# PGTN034_quantizer_mki_controls.net
KiCad netlist of a schematic drawn in EAGLE
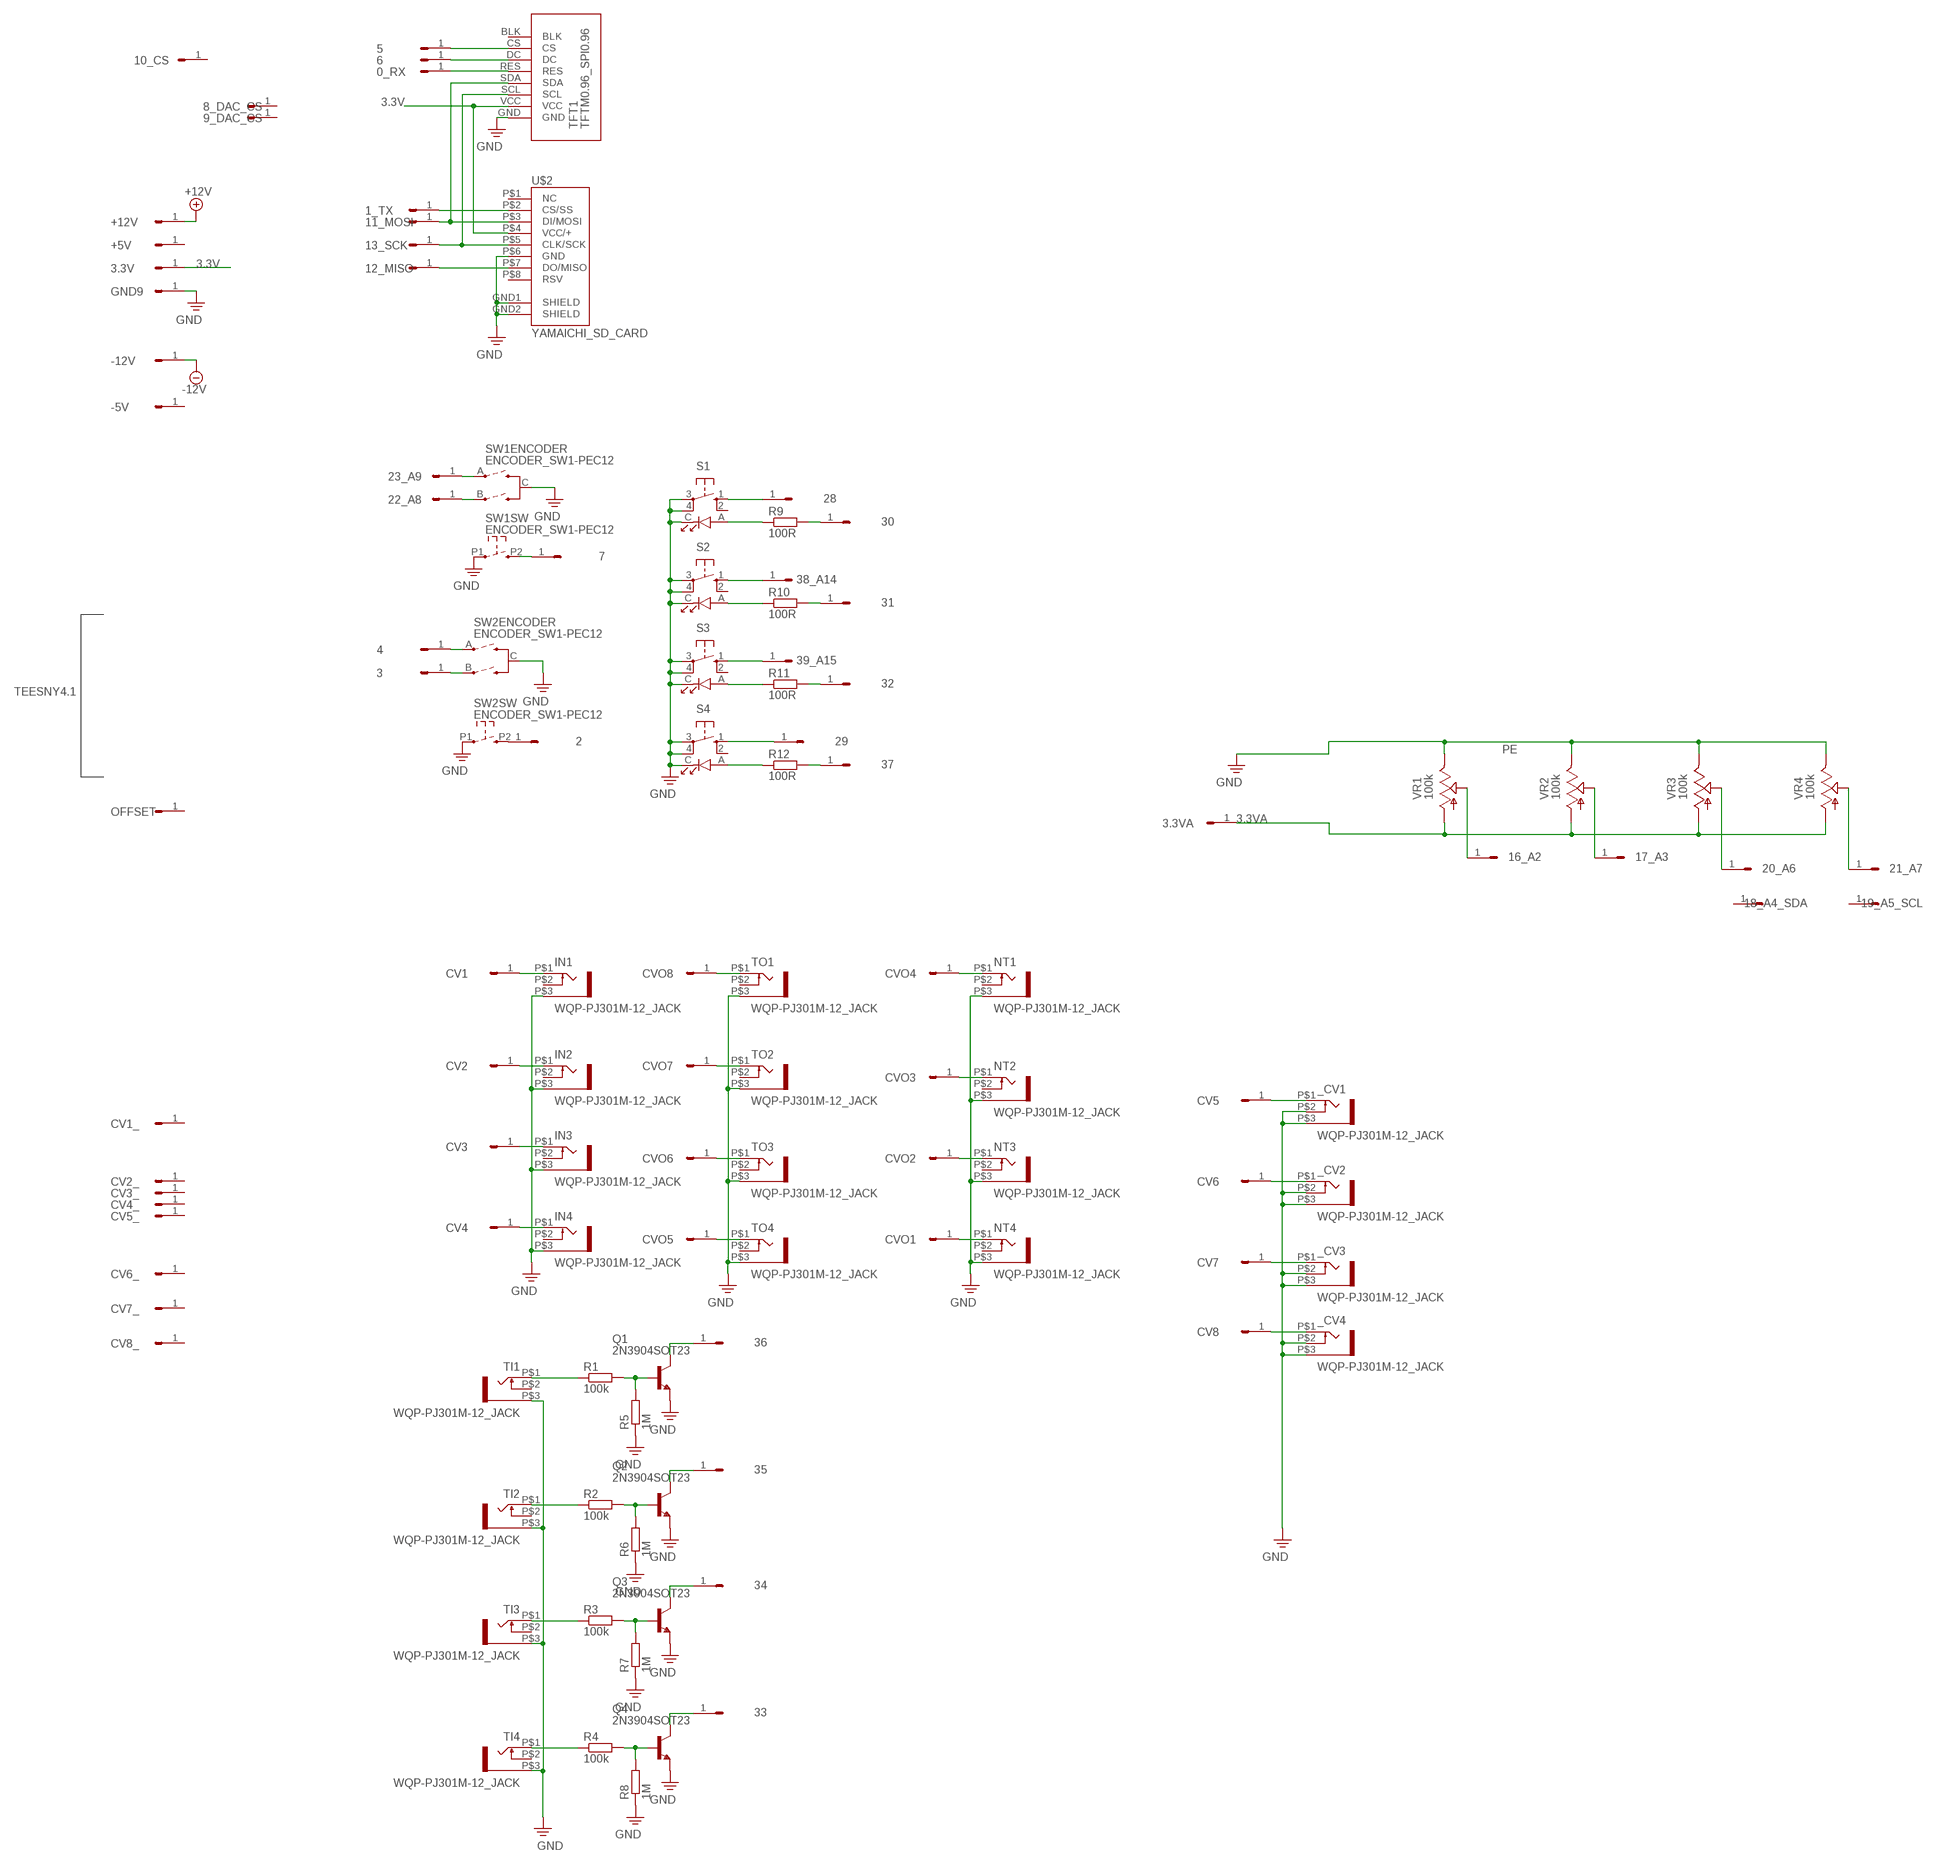
[diagram p0: schematic, sheet 1]

(export (version "E")
  (design (tool "Eeschema 10.0.6"))
  (components
    (comp (ref "+5V")
      (value "HEADER/MALE/01")
      (footprint "eagle-import:HEADER_MALE_01")
      (fields (field (name "SPICEPREFIX") "X"))
      (libsource (lib "eagle-import") (part "HEADER/MALE/01"))
    )
    (comp (ref "+12V")
      (value "HEADER/MALE/01")
      (footprint "eagle-import:HEADER_MALE_01")
      (fields (field (name "SPICEPREFIX") "X"))
      (libsource (lib "eagle-import") (part "HEADER/MALE/01"))
    )
    (comp (ref "-5V")
      (value "HEADER/MALE/01")
      (footprint "eagle-import:HEADER_MALE_01")
      (fields (field (name "SPICEPREFIX") "X"))
      (libsource (lib "eagle-import") (part "HEADER/MALE/01"))
    )
    (comp (ref "-12V")
      (value "HEADER/MALE/01")
      (footprint "eagle-import:HEADER_MALE_01")
      (fields (field (name "SPICEPREFIX") "X"))
      (libsource (lib "eagle-import") (part "HEADER/MALE/01"))
    )
    (comp (ref "0_RX")
      (value "HEADER/MALE/01")
      (footprint "eagle-import:HEADER_MALE_01")
      (fields (field (name "SPICEPREFIX") "X"))
      (libsource (lib "eagle-import") (part "HEADER/MALE/01"))
    )
    (comp (ref "1_TX")
      (value "HEADER/MALE/01")
      (footprint "eagle-import:HEADER_MALE_01")
      (fields (field (name "SPICEPREFIX") "X"))
      (libsource (lib "eagle-import") (part "HEADER/MALE/01"))
    )
    (comp (ref "2")
      (value "HEADER/MALE/01")
      (footprint "eagle-import:HEADER_MALE_01")
      (fields (field (name "SPICEPREFIX") "X"))
      (libsource (lib "eagle-import") (part "HEADER/MALE/01"))
    )
    (comp (ref "3")
      (value "HEADER/MALE/01")
      (footprint "eagle-import:HEADER_MALE_01")
      (fields (field (name "SPICEPREFIX") "X"))
      (libsource (lib "eagle-import") (part "HEADER/MALE/01"))
    )
    (comp (ref "3.3V")
      (value "HEADER/MALE/01")
      (footprint "eagle-import:HEADER_MALE_01")
      (fields (field (name "SPICEPREFIX") "X"))
      (libsource (lib "eagle-import") (part "HEADER/MALE/01"))
    )
    (comp (ref "3.3VA")
      (value "HEADER/MALE/01")
      (footprint "eagle-import:HEADER_MALE_01")
      (fields (field (name "SPICEPREFIX") "X"))
      (libsource (lib "eagle-import") (part "HEADER/MALE/01"))
    )
    (comp (ref "4")
      (value "HEADER/MALE/01")
      (footprint "eagle-import:HEADER_MALE_01")
      (fields (field (name "SPICEPREFIX") "X"))
      (libsource (lib "eagle-import") (part "HEADER/MALE/01"))
    )
    (comp (ref "5")
      (value "HEADER/MALE/01")
      (footprint "eagle-import:HEADER_MALE_01")
      (fields (field (name "SPICEPREFIX") "X"))
      (libsource (lib "eagle-import") (part "HEADER/MALE/01"))
    )
    (comp (ref "6")
      (value "HEADER/MALE/01")
      (footprint "eagle-import:HEADER_MALE_01")
      (fields (field (name "SPICEPREFIX") "X"))
      (libsource (lib "eagle-import") (part "HEADER/MALE/01"))
    )
    (comp (ref "7")
      (value "HEADER/MALE/01")
      (footprint "eagle-import:HEADER_MALE_01")
      (fields (field (name "SPICEPREFIX") "X"))
      (libsource (lib "eagle-import") (part "HEADER/MALE/01"))
    )
    (comp (ref "8_DAC_CS")
      (value "HEADER/MALE/01")
      (footprint "eagle-import:HEADER_MALE_01")
      (fields (field (name "SPICEPREFIX") "X"))
      (libsource (lib "eagle-import") (part "HEADER/MALE/01"))
    )
    (comp (ref "9_DAC_CS")
      (value "HEADER/MALE/01")
      (footprint "eagle-import:HEADER_MALE_01")
      (fields (field (name "SPICEPREFIX") "X"))
      (libsource (lib "eagle-import") (part "HEADER/MALE/01"))
    )
    (comp (ref "10_CS")
      (value "HEADER/MALE/01")
      (footprint "eagle-import:HEADER_MALE_01")
      (fields (field (name "SPICEPREFIX") "X"))
      (libsource (lib "eagle-import") (part "HEADER/MALE/01"))
    )
    (comp (ref "11_MOSI")
      (value "HEADER/MALE/01")
      (footprint "eagle-import:HEADER_MALE_01")
      (fields (field (name "SPICEPREFIX") "X"))
      (libsource (lib "eagle-import") (part "HEADER/MALE/01"))
    )
    (comp (ref "12_MISO")
      (value "HEADER/MALE/01")
      (footprint "eagle-import:HEADER_MALE_01")
      (fields (field (name "SPICEPREFIX") "X"))
      (libsource (lib "eagle-import") (part "HEADER/MALE/01"))
    )
    (comp (ref "13_SCK")
      (value "HEADER/MALE/01")
      (footprint "eagle-import:HEADER_MALE_01")
      (fields (field (name "SPICEPREFIX") "X"))
      (libsource (lib "eagle-import") (part "HEADER/MALE/01"))
    )
    (comp (ref "16_A2")
      (value "HEADER/MALE/01")
      (footprint "eagle-import:HEADER_MALE_01")
      (fields (field (name "SPICEPREFIX") "X"))
      (libsource (lib "eagle-import") (part "HEADER/MALE/01"))
    )
    (comp (ref "17_A3")
      (value "HEADER/MALE/01")
      (footprint "eagle-import:HEADER_MALE_01")
      (fields (field (name "SPICEPREFIX") "X"))
      (libsource (lib "eagle-import") (part "HEADER/MALE/01"))
    )
    (comp (ref "18_A4_SDA")
      (value "HEADER/MALE/01")
      (footprint "eagle-import:HEADER_MALE_01")
      (fields (field (name "SPICEPREFIX") "X"))
      (libsource (lib "eagle-import") (part "HEADER/MALE/01"))
    )
    (comp (ref "19_A5_SCL")
      (value "HEADER/MALE/01")
      (footprint "eagle-import:HEADER_MALE_01")
      (fields (field (name "SPICEPREFIX") "X"))
      (libsource (lib "eagle-import") (part "HEADER/MALE/01"))
    )
    (comp (ref "20_A6")
      (value "HEADER/MALE/01")
      (footprint "eagle-import:HEADER_MALE_01")
      (fields (field (name "SPICEPREFIX") "X"))
      (libsource (lib "eagle-import") (part "HEADER/MALE/01"))
    )
    (comp (ref "21_A7")
      (value "HEADER/MALE/01")
      (footprint "eagle-import:HEADER_MALE_01")
      (fields (field (name "SPICEPREFIX") "X"))
      (libsource (lib "eagle-import") (part "HEADER/MALE/01"))
    )
    (comp (ref "22_A8")
      (value "HEADER/MALE/01")
      (footprint "eagle-import:HEADER_MALE_01")
      (fields (field (name "SPICEPREFIX") "X"))
      (libsource (lib "eagle-import") (part "HEADER/MALE/01"))
    )
    (comp (ref "23_A9")
      (value "HEADER/MALE/01")
      (footprint "eagle-import:HEADER_MALE_01")
      (fields (field (name "SPICEPREFIX") "X"))
      (libsource (lib "eagle-import") (part "HEADER/MALE/01"))
    )
    (comp (ref "28")
      (value "HEADER/MALE/01")
      (footprint "eagle-import:HEADER_MALE_01")
      (fields (field (name "SPICEPREFIX") "X"))
      (libsource (lib "eagle-import") (part "HEADER/MALE/01"))
    )
    (comp (ref "29")
      (value "HEADER/MALE/01")
      (footprint "eagle-import:HEADER_MALE_01")
      (fields (field (name "SPICEPREFIX") "X"))
      (libsource (lib "eagle-import") (part "HEADER/MALE/01"))
    )
    (comp (ref "30")
      (value "HEADER/MALE/01")
      (footprint "eagle-import:HEADER_MALE_01")
      (fields (field (name "SPICEPREFIX") "X"))
      (libsource (lib "eagle-import") (part "HEADER/MALE/01"))
    )
    (comp (ref "31")
      (value "HEADER/MALE/01")
      (footprint "eagle-import:HEADER_MALE_01")
      (fields (field (name "SPICEPREFIX") "X"))
      (libsource (lib "eagle-import") (part "HEADER/MALE/01"))
    )
    (comp (ref "32")
      (value "HEADER/MALE/01")
      (footprint "eagle-import:HEADER_MALE_01")
      (fields (field (name "SPICEPREFIX") "X"))
      (libsource (lib "eagle-import") (part "HEADER/MALE/01"))
    )
    (comp (ref "33")
      (value "HEADER/MALE/01")
      (footprint "eagle-import:HEADER_MALE_01")
      (fields (field (name "SPICEPREFIX") "X"))
      (libsource (lib "eagle-import") (part "HEADER/MALE/01"))
    )
    (comp (ref "34")
      (value "HEADER/MALE/01")
      (footprint "eagle-import:HEADER_MALE_01")
      (fields (field (name "SPICEPREFIX") "X"))
      (libsource (lib "eagle-import") (part "HEADER/MALE/01"))
    )
    (comp (ref "35")
      (value "HEADER/MALE/01")
      (footprint "eagle-import:HEADER_MALE_01")
      (fields (field (name "SPICEPREFIX") "X"))
      (libsource (lib "eagle-import") (part "HEADER/MALE/01"))
    )
    (comp (ref "36")
      (value "HEADER/MALE/01")
      (footprint "eagle-import:HEADER_MALE_01")
      (fields (field (name "SPICEPREFIX") "X"))
      (libsource (lib "eagle-import") (part "HEADER/MALE/01"))
    )
    (comp (ref "37")
      (value "HEADER/MALE/01")
      (footprint "eagle-import:HEADER_MALE_01")
      (fields (field (name "SPICEPREFIX") "X"))
      (libsource (lib "eagle-import") (part "HEADER/MALE/01"))
    )
    (comp (ref "38_A14")
      (value "HEADER/MALE/01")
      (footprint "eagle-import:HEADER_MALE_01")
      (fields (field (name "SPICEPREFIX") "X"))
      (libsource (lib "eagle-import") (part "HEADER/MALE/01"))
    )
    (comp (ref "39_A15")
      (value "HEADER/MALE/01")
      (footprint "eagle-import:HEADER_MALE_01")
      (fields (field (name "SPICEPREFIX") "X"))
      (libsource (lib "eagle-import") (part "HEADER/MALE/01"))
    )
    (comp (ref "CV1")
      (value "HEADER/MALE/01")
      (footprint "eagle-import:HEADER_MALE_01")
      (fields (field (name "SPICEPREFIX") "X"))
      (libsource (lib "eagle-import") (part "HEADER/MALE/01"))
    )
    (comp (ref "CV1_")
      (value "HEADER/MALE/01")
      (footprint "eagle-import:HEADER_MALE_01")
      (fields (field (name "SPICEPREFIX") "X"))
      (libsource (lib "eagle-import") (part "HEADER/MALE/01"))
    )
    (comp (ref "CV2")
      (value "HEADER/MALE/01")
      (footprint "eagle-import:HEADER_MALE_01")
      (fields (field (name "SPICEPREFIX") "X"))
      (libsource (lib "eagle-import") (part "HEADER/MALE/01"))
    )
    (comp (ref "CV2_")
      (value "HEADER/MALE/01")
      (footprint "eagle-import:HEADER_MALE_01")
      (fields (field (name "SPICEPREFIX") "X"))
      (libsource (lib "eagle-import") (part "HEADER/MALE/01"))
    )
    (comp (ref "CV3")
      (value "HEADER/MALE/01")
      (footprint "eagle-import:HEADER_MALE_01")
      (fields (field (name "SPICEPREFIX") "X"))
      (libsource (lib "eagle-import") (part "HEADER/MALE/01"))
    )
    (comp (ref "CV3_")
      (value "HEADER/MALE/01")
      (footprint "eagle-import:HEADER_MALE_01")
      (fields (field (name "SPICEPREFIX") "X"))
      (libsource (lib "eagle-import") (part "HEADER/MALE/01"))
    )
    (comp (ref "CV4")
      (value "HEADER/MALE/01")
      (footprint "eagle-import:HEADER_MALE_01")
      (fields (field (name "SPICEPREFIX") "X"))
      (libsource (lib "eagle-import") (part "HEADER/MALE/01"))
    )
    (comp (ref "CV4_")
      (value "HEADER/MALE/01")
      (footprint "eagle-import:HEADER_MALE_01")
      (fields (field (name "SPICEPREFIX") "X"))
      (libsource (lib "eagle-import") (part "HEADER/MALE/01"))
    )
    (comp (ref "CV5")
      (value "HEADER/MALE/01")
      (footprint "eagle-import:HEADER_MALE_01")
      (fields (field (name "SPICEPREFIX") "X"))
      (libsource (lib "eagle-import") (part "HEADER/MALE/01"))
    )
    (comp (ref "CV5_")
      (value "HEADER/MALE/01")
      (footprint "eagle-import:HEADER_MALE_01")
      (fields (field (name "SPICEPREFIX") "X"))
      (libsource (lib "eagle-import") (part "HEADER/MALE/01"))
    )
    (comp (ref "CV6")
      (value "HEADER/MALE/01")
      (footprint "eagle-import:HEADER_MALE_01")
      (fields (field (name "SPICEPREFIX") "X"))
      (libsource (lib "eagle-import") (part "HEADER/MALE/01"))
    )
    (comp (ref "CV6_")
      (value "HEADER/MALE/01")
      (footprint "eagle-import:HEADER_MALE_01")
      (fields (field (name "SPICEPREFIX") "X"))
      (libsource (lib "eagle-import") (part "HEADER/MALE/01"))
    )
    (comp (ref "CV7")
      (value "HEADER/MALE/01")
      (footprint "eagle-import:HEADER_MALE_01")
      (fields (field (name "SPICEPREFIX") "X"))
      (libsource (lib "eagle-import") (part "HEADER/MALE/01"))
    )
    (comp (ref "CV7_")
      (value "HEADER/MALE/01")
      (footprint "eagle-import:HEADER_MALE_01")
      (fields (field (name "SPICEPREFIX") "X"))
      (libsource (lib "eagle-import") (part "HEADER/MALE/01"))
    )
    (comp (ref "CV8")
      (value "HEADER/MALE/01")
      (footprint "eagle-import:HEADER_MALE_01")
      (fields (field (name "SPICEPREFIX") "X"))
      (libsource (lib "eagle-import") (part "HEADER/MALE/01"))
    )
    (comp (ref "CV8_")
      (value "HEADER/MALE/01")
      (footprint "eagle-import:HEADER_MALE_01")
      (fields (field (name "SPICEPREFIX") "X"))
      (libsource (lib "eagle-import") (part "HEADER/MALE/01"))
    )
    (comp (ref "CVO1")
      (value "HEADER/MALE/01")
      (footprint "eagle-import:HEADER_MALE_01")
      (fields (field (name "SPICEPREFIX") "X"))
      (libsource (lib "eagle-import") (part "HEADER/MALE/01"))
    )
    (comp (ref "CVO2")
      (value "HEADER/MALE/01")
      (footprint "eagle-import:HEADER_MALE_01")
      (fields (field (name "SPICEPREFIX") "X"))
      (libsource (lib "eagle-import") (part "HEADER/MALE/01"))
    )
    (comp (ref "CVO3")
      (value "HEADER/MALE/01")
      (footprint "eagle-import:HEADER_MALE_01")
      (fields (field (name "SPICEPREFIX") "X"))
      (libsource (lib "eagle-import") (part "HEADER/MALE/01"))
    )
    (comp (ref "CVO4")
      (value "HEADER/MALE/01")
      (footprint "eagle-import:HEADER_MALE_01")
      (fields (field (name "SPICEPREFIX") "X"))
      (libsource (lib "eagle-import") (part "HEADER/MALE/01"))
    )
    (comp (ref "CVO5")
      (value "HEADER/MALE/01")
      (footprint "eagle-import:HEADER_MALE_01")
      (fields (field (name "SPICEPREFIX") "X"))
      (libsource (lib "eagle-import") (part "HEADER/MALE/01"))
    )
    (comp (ref "CVO6")
      (value "HEADER/MALE/01")
      (footprint "eagle-import:HEADER_MALE_01")
      (fields (field (name "SPICEPREFIX") "X"))
      (libsource (lib "eagle-import") (part "HEADER/MALE/01"))
    )
    (comp (ref "CVO7")
      (value "HEADER/MALE/01")
      (footprint "eagle-import:HEADER_MALE_01")
      (fields (field (name "SPICEPREFIX") "X"))
      (libsource (lib "eagle-import") (part "HEADER/MALE/01"))
    )
    (comp (ref "CVO8")
      (value "HEADER/MALE/01")
      (footprint "eagle-import:HEADER_MALE_01")
      (fields (field (name "SPICEPREFIX") "X"))
      (libsource (lib "eagle-import") (part "HEADER/MALE/01"))
    )
    (comp (ref "GND9")
      (value "HEADER/MALE/01")
      (footprint "eagle-import:HEADER_MALE_01")
      (fields (field (name "SPICEPREFIX") "X"))
      (libsource (lib "eagle-import") (part "HEADER/MALE/01"))
    )
    (comp (ref "IN1")
      (value "WQP-PJ301M-12_JACK")
      (footprint "eagle-import:WQP-PJ301M-12_JACK")
      (libsource (lib "eagle-import") (part "WQP-PJ301M-12_JACK"))
    )
    (comp (ref "IN2")
      (value "WQP-PJ301M-12_JACK")
      (footprint "eagle-import:WQP-PJ301M-12_JACK")
      (libsource (lib "eagle-import") (part "WQP-PJ301M-12_JACK"))
    )
    (comp (ref "IN3")
      (value "WQP-PJ301M-12_JACK")
      (footprint "eagle-import:WQP-PJ301M-12_JACK")
      (libsource (lib "eagle-import") (part "WQP-PJ301M-12_JACK"))
    )
    (comp (ref "IN4")
      (value "WQP-PJ301M-12_JACK")
      (footprint "eagle-import:WQP-PJ301M-12_JACK")
      (libsource (lib "eagle-import") (part "WQP-PJ301M-12_JACK"))
    )
    (comp (ref "NT1")
      (value "WQP-PJ301M-12_JACK")
      (footprint "eagle-import:WQP-PJ301M-12_JACK")
      (libsource (lib "eagle-import") (part "WQP-PJ301M-12_JACK"))
    )
    (comp (ref "NT2")
      (value "WQP-PJ301M-12_JACK")
      (footprint "eagle-import:WQP-PJ301M-12_JACK")
      (libsource (lib "eagle-import") (part "WQP-PJ301M-12_JACK"))
    )
    (comp (ref "NT3")
      (value "WQP-PJ301M-12_JACK")
      (footprint "eagle-import:WQP-PJ301M-12_JACK")
      (libsource (lib "eagle-import") (part "WQP-PJ301M-12_JACK"))
    )
    (comp (ref "NT4")
      (value "WQP-PJ301M-12_JACK")
      (footprint "eagle-import:WQP-PJ301M-12_JACK")
      (libsource (lib "eagle-import") (part "WQP-PJ301M-12_JACK"))
    )
    (comp (ref "OFFSET")
      (value "HEADER/MALE/01")
      (footprint "eagle-import:HEADER_MALE_01")
      (fields (field (name "SPICEPREFIX") "X"))
      (libsource (lib "eagle-import") (part "HEADER/MALE/01"))
    )
    (comp (ref "Q1")
      (value "2N3904SOT23")
      (footprint "eagle-import:SOT23")
      (libsource (lib "eagle-import") (part "2N3904SOT23"))
    )
    (comp (ref "Q2")
      (value "2N3904SOT23")
      (footprint "eagle-import:SOT23")
      (libsource (lib "eagle-import") (part "2N3904SOT23"))
    )
    (comp (ref "Q3")
      (value "2N3904SOT23")
      (footprint "eagle-import:SOT23")
      (libsource (lib "eagle-import") (part "2N3904SOT23"))
    )
    (comp (ref "Q4")
      (value "2N3904SOT23")
      (footprint "eagle-import:SOT23")
      (libsource (lib "eagle-import") (part "2N3904SOT23"))
    )
    (comp (ref "R1")
      (value "100k")
      (footprint "eagle-import:R0603")
      (libsource (lib "eagle-import") (part "RESISTOR"))
    )
    (comp (ref "R2")
      (value "100k")
      (footprint "eagle-import:R0603")
      (libsource (lib "eagle-import") (part "RESISTOR"))
    )
    (comp (ref "R3")
      (value "100k")
      (footprint "eagle-import:R0603")
      (libsource (lib "eagle-import") (part "RESISTOR"))
    )
    (comp (ref "R4")
      (value "100k")
      (footprint "eagle-import:R0603")
      (libsource (lib "eagle-import") (part "RESISTOR"))
    )
    (comp (ref "R5")
      (value "1M")
      (footprint "eagle-import:R0603")
      (libsource (lib "eagle-import") (part "RESISTOR"))
    )
    (comp (ref "R6")
      (value "1M")
      (footprint "eagle-import:R0603")
      (libsource (lib "eagle-import") (part "RESISTOR"))
    )
    (comp (ref "R7")
      (value "1M")
      (footprint "eagle-import:R0603")
      (libsource (lib "eagle-import") (part "RESISTOR"))
    )
    (comp (ref "R8")
      (value "1M")
      (footprint "eagle-import:R0603")
      (libsource (lib "eagle-import") (part "RESISTOR"))
    )
    (comp (ref "R9")
      (value "100R")
      (footprint "eagle-import:R0603")
      (libsource (lib "eagle-import") (part "RESISTOR"))
    )
    (comp (ref "R10")
      (value "100R")
      (footprint "eagle-import:R0603")
      (libsource (lib "eagle-import") (part "RESISTOR"))
    )
    (comp (ref "R11")
      (value "100R")
      (footprint "eagle-import:R0603")
      (libsource (lib "eagle-import") (part "RESISTOR"))
    )
    (comp (ref "R12")
      (value "100R")
      (footprint "eagle-import:R0603")
      (libsource (lib "eagle-import") (part "RESISTOR"))
    )
    (comp (ref "S1")
      (value "SW-LEDTHONK")
      (footprint "eagle-import:SW-PUSH-TACT-LED-THONK")
      (libsource (lib "eagle-import") (part "SW-LEDTHONK"))
    )
    (comp (ref "S2")
      (value "SW-LEDTHONK")
      (footprint "eagle-import:SW-PUSH-TACT-LED-THONK")
      (libsource (lib "eagle-import") (part "SW-LEDTHONK"))
    )
    (comp (ref "S3")
      (value "SW-LEDTHONK")
      (footprint "eagle-import:SW-PUSH-TACT-LED-THONK")
      (libsource (lib "eagle-import") (part "SW-LEDTHONK"))
    )
    (comp (ref "S4")
      (value "SW-LEDTHONK")
      (footprint "eagle-import:SW-PUSH-TACT-LED-THONK")
      (libsource (lib "eagle-import") (part "SW-LEDTHONK"))
    )
    (comp (ref "SW1")
      (value "ENCODER_SW1-PEC12")
      (footprint "eagle-import:PEC12_INCREMENTAL_ENCODER")
      (libsource (lib "eagle-import") (part "ENCODER_SW1-PEC12"))
    )
    (comp (ref "SW2")
      (value "ENCODER_SW1-PEC12")
      (footprint "eagle-import:PEC12_INCREMENTAL_ENCODER")
      (libsource (lib "eagle-import") (part "ENCODER_SW1-PEC12"))
    )
    (comp (ref "TFT1")
      (value "TFTM0.96_SPI0.96")
      (footprint "eagle-import:TFTM0.96")
      (libsource (lib "eagle-import") (part "TFTM0.96_SPI0.96"))
    )
    (comp (ref "TI1")
      (value "WQP-PJ301M-12_JACK")
      (footprint "eagle-import:WQP-PJ301M-12_JACK")
      (fields (field (name "SPICEPREFIX") "J"))
      (libsource (lib "eagle-import") (part "WQP-PJ301M-12_JACK"))
    )
    (comp (ref "TI2")
      (value "WQP-PJ301M-12_JACK")
      (footprint "eagle-import:WQP-PJ301M-12_JACK")
      (fields (field (name "SPICEPREFIX") "J"))
      (libsource (lib "eagle-import") (part "WQP-PJ301M-12_JACK"))
    )
    (comp (ref "TI3")
      (value "WQP-PJ301M-12_JACK")
      (footprint "eagle-import:WQP-PJ301M-12_JACK")
      (fields (field (name "SPICEPREFIX") "J"))
      (libsource (lib "eagle-import") (part "WQP-PJ301M-12_JACK"))
    )
    (comp (ref "TI4")
      (value "WQP-PJ301M-12_JACK")
      (footprint "eagle-import:WQP-PJ301M-12_JACK")
      (fields (field (name "SPICEPREFIX") "J"))
      (libsource (lib "eagle-import") (part "WQP-PJ301M-12_JACK"))
    )
    (comp (ref "TO1")
      (value "WQP-PJ301M-12_JACK")
      (footprint "eagle-import:WQP-PJ301M-12_JACK")
      (libsource (lib "eagle-import") (part "WQP-PJ301M-12_JACK"))
    )
    (comp (ref "TO2")
      (value "WQP-PJ301M-12_JACK")
      (footprint "eagle-import:WQP-PJ301M-12_JACK")
      (libsource (lib "eagle-import") (part "WQP-PJ301M-12_JACK"))
    )
    (comp (ref "TO3")
      (value "WQP-PJ301M-12_JACK")
      (footprint "eagle-import:WQP-PJ301M-12_JACK")
      (libsource (lib "eagle-import") (part "WQP-PJ301M-12_JACK"))
    )
    (comp (ref "TO4")
      (value "WQP-PJ301M-12_JACK")
      (footprint "eagle-import:WQP-PJ301M-12_JACK")
      (libsource (lib "eagle-import") (part "WQP-PJ301M-12_JACK"))
    )
    (comp (ref "U$2")
      (value "YAMAICHI_SD_CARD")
      (footprint "eagle-import:YAMAICHI_MICROSD_VERTICAL")
      (libsource (lib "eagle-import") (part "YAMAICHI_SD_CARD"))
    )
    (comp (ref "VR1")
      (value "100k")
      (footprint "eagle-import:9MM_SNAP-IN_POT")
      (libsource (lib "eagle-import") (part "9MM_SNAP-IN_POT_"))
    )
    (comp (ref "VR2")
      (value "100k")
      (footprint "eagle-import:9MM_SNAP-IN_POT")
      (libsource (lib "eagle-import") (part "9MM_SNAP-IN_POT_"))
    )
    (comp (ref "VR3")
      (value "100k")
      (footprint "eagle-import:9MM_SNAP-IN_POT")
      (libsource (lib "eagle-import") (part "9MM_SNAP-IN_POT_"))
    )
    (comp (ref "VR4")
      (value "100k")
      (footprint "eagle-import:9MM_SNAP-IN_POT")
      (libsource (lib "eagle-import") (part "9MM_SNAP-IN_POT_"))
    )
    (comp (ref "_CV1")
      (value "WQP-PJ301M-12_JACK")
      (footprint "eagle-import:WQP-PJ301M-12_JACK")
      (libsource (lib "eagle-import") (part "WQP-PJ301M-12_JACK"))
    )
    (comp (ref "_CV2")
      (value "WQP-PJ301M-12_JACK")
      (footprint "eagle-import:WQP-PJ301M-12_JACK")
      (libsource (lib "eagle-import") (part "WQP-PJ301M-12_JACK"))
    )
    (comp (ref "_CV3")
      (value "WQP-PJ301M-12_JACK")
      (footprint "eagle-import:WQP-PJ301M-12_JACK")
      (libsource (lib "eagle-import") (part "WQP-PJ301M-12_JACK"))
    )
    (comp (ref "_CV4")
      (value "WQP-PJ301M-12_JACK")
      (footprint "eagle-import:WQP-PJ301M-12_JACK")
      (libsource (lib "eagle-import") (part "WQP-PJ301M-12_JACK"))
    )
  )
  (nets
    (net (code "1") (name "+12V") (class "Default")
      (node (ref "+12V") (pin "1") (pinfunction "3_1") (pintype "passive"))
    )
    (net (code "2") (name "-12V") (class "Default")
      (node (ref "-12V") (pin "1") (pinfunction "3_1") (pintype "passive"))
    )
    (net (code "3") (name "/3.3V") (class "Default")
      (node (ref "3.3V") (pin "1") (pinfunction "3_1") (pintype "passive"))
      (node (ref "TFT1") (pin "VCC") (pinfunction "VCC_VCC") (pintype "bidirectional"))
      (node (ref "U$2") (pin "P$4") (pinfunction "VCC/+_P$4") (pintype "bidirectional"))
    )
    (net (code "4") (name "/3.3VA") (class "Default")
      (node (ref "3.3VA") (pin "1") (pinfunction "3_1") (pintype "passive"))
      (node (ref "VR1") (pin "1") (pinfunction "A_1") (pintype "passive"))
      (node (ref "VR2") (pin "1") (pinfunction "A_1") (pintype "passive"))
      (node (ref "VR3") (pin "1") (pinfunction "A_1") (pintype "passive"))
      (node (ref "VR4") (pin "1") (pinfunction "A_1") (pintype "passive"))
    )
    (net (code "5") (name "GND") (class "Default")
      (node (ref "GND9") (pin "1") (pinfunction "3_1") (pintype "passive"))
      (node (ref "IN1") (pin "P$3") (pinfunction "1_P$3") (pintype "passive"))
      (node (ref "IN2") (pin "P$3") (pinfunction "1_P$3") (pintype "passive"))
      (node (ref "IN3") (pin "P$3") (pinfunction "1_P$3") (pintype "passive"))
      (node (ref "IN4") (pin "P$3") (pinfunction "1_P$3") (pintype "passive"))
      (node (ref "NT1") (pin "P$3") (pinfunction "1_P$3") (pintype "passive"))
      (node (ref "NT2") (pin "P$3") (pinfunction "1_P$3") (pintype "passive"))
      (node (ref "NT3") (pin "P$3") (pinfunction "1_P$3") (pintype "passive"))
      (node (ref "NT4") (pin "P$3") (pinfunction "1_P$3") (pintype "passive"))
      (node (ref "Q1") (pin "2") (pinfunction "E_2") (pintype "passive"))
      (node (ref "Q2") (pin "2") (pinfunction "E_2") (pintype "passive"))
      (node (ref "Q3") (pin "2") (pinfunction "E_2") (pintype "passive"))
      (node (ref "Q4") (pin "2") (pinfunction "E_2") (pintype "passive"))
      (node (ref "R5") (pin "1") (pinfunction "1_1") (pintype "passive"))
      (node (ref "R6") (pin "1") (pinfunction "1_1") (pintype "passive"))
      (node (ref "R7") (pin "1") (pinfunction "1_1") (pintype "passive"))
      (node (ref "R8") (pin "1") (pinfunction "1_1") (pintype "passive"))
      (node (ref "S1") (pin "3") (pinfunction "P_3") (pintype "passive"))
      (node (ref "S1") (pin "4") (pinfunction "P1_4") (pintype "passive"))
      (node (ref "S1") (pin "C") (pinfunction "C_C") (pintype "passive"))
      (node (ref "S2") (pin "3") (pinfunction "P_3") (pintype "passive"))
      (node (ref "S2") (pin "4") (pinfunction "P1_4") (pintype "passive"))
      (node (ref "S2") (pin "C") (pinfunction "C_C") (pintype "passive"))
      (node (ref "S3") (pin "3") (pinfunction "P_3") (pintype "passive"))
      (node (ref "S3") (pin "4") (pinfunction "P1_4") (pintype "passive"))
      (node (ref "S3") (pin "C") (pinfunction "C_C") (pintype "passive"))
      (node (ref "S4") (pin "3") (pinfunction "P_3") (pintype "passive"))
      (node (ref "S4") (pin "4") (pinfunction "P1_4") (pintype "passive"))
      (node (ref "S4") (pin "C") (pinfunction "C_C") (pintype "passive"))
      (node (ref "SW1") (pin "C") (pinfunction "C_C") (pintype "passive"))
      (node (ref "SW1") (pin "P1") (pinfunction "1_P1") (pintype "passive"))
      (node (ref "SW2") (pin "C") (pinfunction "C_C") (pintype "passive"))
      (node (ref "SW2") (pin "P1") (pinfunction "1_P1") (pintype "passive"))
      (node (ref "TFT1") (pin "GND") (pinfunction "GND_GND") (pintype "bidirectional"))
      (node (ref "TI1") (pin "P$3") (pinfunction "1_P$3") (pintype "passive"))
      (node (ref "TI2") (pin "P$3") (pinfunction "1_P$3") (pintype "passive"))
      (node (ref "TI3") (pin "P$3") (pinfunction "1_P$3") (pintype "passive"))
      (node (ref "TI4") (pin "P$3") (pinfunction "1_P$3") (pintype "passive"))
      (node (ref "TO1") (pin "P$3") (pinfunction "1_P$3") (pintype "passive"))
      (node (ref "TO2") (pin "P$3") (pinfunction "1_P$3") (pintype "passive"))
      (node (ref "TO3") (pin "P$3") (pinfunction "1_P$3") (pintype "passive"))
      (node (ref "TO4") (pin "P$3") (pinfunction "1_P$3") (pintype "passive"))
      (node (ref "U$2") (pin "GND1") (pinfunction "SHIELD_GND1") (pintype "bidirectional"))
      (node (ref "U$2") (pin "GND2") (pinfunction "SHIELD_GND2") (pintype "bidirectional"))
      (node (ref "U$2") (pin "P$6") (pinfunction "GND_P$6") (pintype "bidirectional"))
      (node (ref "VR1") (pin "3") (pinfunction "E_3") (pintype "passive"))
      (node (ref "VR2") (pin "3") (pinfunction "E_3") (pintype "passive"))
      (node (ref "VR3") (pin "3") (pinfunction "E_3") (pintype "passive"))
      (node (ref "VR4") (pin "3") (pinfunction "E_3") (pintype "passive"))
      (node (ref "_CV1") (pin "P$2") (pinfunction "3_P$2") (pintype "passive"))
      (node (ref "_CV1") (pin "P$3") (pinfunction "1_P$3") (pintype "passive"))
      (node (ref "_CV2") (pin "P$2") (pinfunction "3_P$2") (pintype "passive"))
      (node (ref "_CV2") (pin "P$3") (pinfunction "1_P$3") (pintype "passive"))
      (node (ref "_CV3") (pin "P$2") (pinfunction "3_P$2") (pintype "passive"))
      (node (ref "_CV3") (pin "P$3") (pinfunction "1_P$3") (pintype "passive"))
      (node (ref "_CV4") (pin "P$2") (pinfunction "3_P$2") (pintype "passive"))
      (node (ref "_CV4") (pin "P$3") (pinfunction "1_P$3") (pintype "passive"))
    )
    (net (code "6") (name "Net-(0_RX-3)") (class "Default")
      (node (ref "0_RX") (pin "1") (pinfunction "3_1") (pintype "passive"))
      (node (ref "TFT1") (pin "RES") (pinfunction "RES_RES") (pintype "bidirectional"))
    )
    (net (code "7") (name "Net-(1_TX-3)") (class "Default")
      (node (ref "1_TX") (pin "1") (pinfunction "3_1") (pintype "passive"))
      (node (ref "U$2") (pin "P$2") (pinfunction "CS/SS_P$2") (pintype "bidirectional"))
    )
    (net (code "8") (name "Net-(2-3)") (class "Default")
      (node (ref "2") (pin "1") (pinfunction "3_1") (pintype "passive"))
      (node (ref "SW2") (pin "P2") (pinfunction "2_P2") (pintype "passive"))
    )
    (net (code "9") (name "Net-(3-3)") (class "Default")
      (node (ref "3") (pin "1") (pinfunction "3_1") (pintype "passive"))
      (node (ref "SW2") (pin "B") (pinfunction "B_B") (pintype "passive"))
    )
    (net (code "10") (name "Net-(4-3)") (class "Default")
      (node (ref "4") (pin "1") (pinfunction "3_1") (pintype "passive"))
      (node (ref "SW2") (pin "A") (pinfunction "A_A") (pintype "passive"))
    )
    (net (code "11") (name "Net-(5-3)") (class "Default")
      (node (ref "5") (pin "1") (pinfunction "3_1") (pintype "passive"))
      (node (ref "TFT1") (pin "CS") (pinfunction "CS_CS") (pintype "bidirectional"))
    )
    (net (code "12") (name "Net-(6-3)") (class "Default")
      (node (ref "6") (pin "1") (pinfunction "3_1") (pintype "passive"))
      (node (ref "TFT1") (pin "DC") (pinfunction "DC_DC") (pintype "bidirectional"))
    )
    (net (code "13") (name "Net-(7-3)") (class "Default")
      (node (ref "7") (pin "1") (pinfunction "3_1") (pintype "passive"))
      (node (ref "SW1") (pin "P2") (pinfunction "2_P2") (pintype "passive"))
    )
    (net (code "14") (name "Net-(11_MOSI-3)") (class "Default")
      (node (ref "11_MOSI") (pin "1") (pinfunction "3_1") (pintype "passive"))
      (node (ref "TFT1") (pin "SDA") (pinfunction "SDA_SDA") (pintype "bidirectional"))
      (node (ref "U$2") (pin "P$3") (pinfunction "DI/MOSI_P$3") (pintype "bidirectional"))
    )
    (net (code "15") (name "Net-(12_MISO-3)") (class "Default")
      (node (ref "12_MISO") (pin "1") (pinfunction "3_1") (pintype "passive"))
      (node (ref "U$2") (pin "P$7") (pinfunction "DO/MISO_P$7") (pintype "bidirectional"))
    )
    (net (code "16") (name "Net-(13_SCK-3)") (class "Default")
      (node (ref "13_SCK") (pin "1") (pinfunction "3_1") (pintype "passive"))
      (node (ref "TFT1") (pin "SCL") (pinfunction "SCL_SCL") (pintype "bidirectional"))
      (node (ref "U$2") (pin "P$5") (pinfunction "CLK/SCK_P$5") (pintype "bidirectional"))
    )
    (net (code "17") (name "Net-(16_A2-3)") (class "Default")
      (node (ref "16_A2") (pin "1") (pinfunction "3_1") (pintype "passive"))
      (node (ref "VR1") (pin "2") (pinfunction "S_2") (pintype "passive"))
    )
    (net (code "18") (name "Net-(17_A3-3)") (class "Default")
      (node (ref "17_A3") (pin "1") (pinfunction "3_1") (pintype "passive"))
      (node (ref "VR2") (pin "2") (pinfunction "S_2") (pintype "passive"))
    )
    (net (code "19") (name "Net-(20_A6-3)") (class "Default")
      (node (ref "20_A6") (pin "1") (pinfunction "3_1") (pintype "passive"))
      (node (ref "VR3") (pin "2") (pinfunction "S_2") (pintype "passive"))
    )
    (net (code "20") (name "Net-(21_A7-3)") (class "Default")
      (node (ref "21_A7") (pin "1") (pinfunction "3_1") (pintype "passive"))
      (node (ref "VR4") (pin "2") (pinfunction "S_2") (pintype "passive"))
    )
    (net (code "21") (name "Net-(22_A8-3)") (class "Default")
      (node (ref "22_A8") (pin "1") (pinfunction "3_1") (pintype "passive"))
      (node (ref "SW1") (pin "B") (pinfunction "B_B") (pintype "passive"))
    )
    (net (code "22") (name "Net-(23_A9-3)") (class "Default")
      (node (ref "23_A9") (pin "1") (pinfunction "3_1") (pintype "passive"))
      (node (ref "SW1") (pin "A") (pinfunction "A_A") (pintype "passive"))
    )
    (net (code "23") (name "Net-(28-3)") (class "Default")
      (node (ref "28") (pin "1") (pinfunction "3_1") (pintype "passive"))
      (node (ref "S1") (pin "1") (pinfunction "S_1") (pintype "passive"))
    )
    (net (code "24") (name "Net-(29-3)") (class "Default")
      (node (ref "29") (pin "1") (pinfunction "3_1") (pintype "passive"))
      (node (ref "S4") (pin "1") (pinfunction "S_1") (pintype "passive"))
    )
    (net (code "25") (name "Net-(30-3)") (class "Default")
      (node (ref "30") (pin "1") (pinfunction "3_1") (pintype "passive"))
      (node (ref "R9") (pin "2") (pinfunction "2_2") (pintype "passive"))
    )
    (net (code "26") (name "Net-(31-3)") (class "Default")
      (node (ref "31") (pin "1") (pinfunction "3_1") (pintype "passive"))
      (node (ref "R10") (pin "2") (pinfunction "2_2") (pintype "passive"))
    )
    (net (code "27") (name "Net-(32-3)") (class "Default")
      (node (ref "32") (pin "1") (pinfunction "3_1") (pintype "passive"))
      (node (ref "R11") (pin "2") (pinfunction "2_2") (pintype "passive"))
    )
    (net (code "28") (name "Net-(33-3)") (class "Default")
      (node (ref "33") (pin "1") (pinfunction "3_1") (pintype "passive"))
      (node (ref "Q4") (pin "3") (pinfunction "C_3") (pintype "passive"))
    )
    (net (code "29") (name "Net-(34-3)") (class "Default")
      (node (ref "34") (pin "1") (pinfunction "3_1") (pintype "passive"))
      (node (ref "Q3") (pin "3") (pinfunction "C_3") (pintype "passive"))
    )
    (net (code "30") (name "Net-(35-3)") (class "Default")
      (node (ref "35") (pin "1") (pinfunction "3_1") (pintype "passive"))
      (node (ref "Q2") (pin "3") (pinfunction "C_3") (pintype "passive"))
    )
    (net (code "31") (name "Net-(36-3)") (class "Default")
      (node (ref "36") (pin "1") (pinfunction "3_1") (pintype "passive"))
      (node (ref "Q1") (pin "3") (pinfunction "C_3") (pintype "passive"))
    )
    (net (code "32") (name "Net-(37-3)") (class "Default")
      (node (ref "37") (pin "1") (pinfunction "3_1") (pintype "passive"))
      (node (ref "R12") (pin "2") (pinfunction "2_2") (pintype "passive"))
    )
    (net (code "33") (name "Net-(38_A14-3)") (class "Default")
      (node (ref "38_A14") (pin "1") (pinfunction "3_1") (pintype "passive"))
      (node (ref "S2") (pin "1") (pinfunction "S_1") (pintype "passive"))
    )
    (net (code "34") (name "Net-(39_A15-3)") (class "Default")
      (node (ref "39_A15") (pin "1") (pinfunction "3_1") (pintype "passive"))
      (node (ref "S3") (pin "1") (pinfunction "S_1") (pintype "passive"))
    )
    (net (code "35") (name "Net-(CV1-3)") (class "Default")
      (node (ref "CV1") (pin "1") (pinfunction "3_1") (pintype "passive"))
      (node (ref "IN1") (pin "P$1") (pinfunction "2_P$1") (pintype "passive"))
    )
    (net (code "36") (name "Net-(CV2-3)") (class "Default")
      (node (ref "CV2") (pin "1") (pinfunction "3_1") (pintype "passive"))
      (node (ref "IN2") (pin "P$1") (pinfunction "2_P$1") (pintype "passive"))
    )
    (net (code "37") (name "Net-(CV3-3)") (class "Default")
      (node (ref "CV3") (pin "1") (pinfunction "3_1") (pintype "passive"))
      (node (ref "IN3") (pin "P$1") (pinfunction "2_P$1") (pintype "passive"))
    )
    (net (code "38") (name "Net-(CV4-3)") (class "Default")
      (node (ref "CV4") (pin "1") (pinfunction "3_1") (pintype "passive"))
      (node (ref "IN4") (pin "P$1") (pinfunction "2_P$1") (pintype "passive"))
    )
    (net (code "39") (name "Net-(CV5-3)") (class "Default")
      (node (ref "CV5") (pin "1") (pinfunction "3_1") (pintype "passive"))
      (node (ref "_CV1") (pin "P$1") (pinfunction "2_P$1") (pintype "passive"))
    )
    (net (code "40") (name "Net-(CV6-3)") (class "Default")
      (node (ref "CV6") (pin "1") (pinfunction "3_1") (pintype "passive"))
      (node (ref "_CV2") (pin "P$1") (pinfunction "2_P$1") (pintype "passive"))
    )
    (net (code "41") (name "Net-(CV7-3)") (class "Default")
      (node (ref "CV7") (pin "1") (pinfunction "3_1") (pintype "passive"))
      (node (ref "_CV3") (pin "P$1") (pinfunction "2_P$1") (pintype "passive"))
    )
    (net (code "42") (name "Net-(CV8-3)") (class "Default")
      (node (ref "CV8") (pin "1") (pinfunction "3_1") (pintype "passive"))
      (node (ref "_CV4") (pin "P$1") (pinfunction "2_P$1") (pintype "passive"))
    )
    (net (code "43") (name "Net-(CVO1-3)") (class "Default")
      (node (ref "CVO1") (pin "1") (pinfunction "3_1") (pintype "passive"))
      (node (ref "NT4") (pin "P$1") (pinfunction "2_P$1") (pintype "passive"))
    )
    (net (code "44") (name "Net-(CVO2-3)") (class "Default")
      (node (ref "CVO2") (pin "1") (pinfunction "3_1") (pintype "passive"))
      (node (ref "NT3") (pin "P$1") (pinfunction "2_P$1") (pintype "passive"))
    )
    (net (code "45") (name "Net-(CVO3-3)") (class "Default")
      (node (ref "CVO3") (pin "1") (pinfunction "3_1") (pintype "passive"))
      (node (ref "NT2") (pin "P$1") (pinfunction "2_P$1") (pintype "passive"))
    )
    (net (code "46") (name "Net-(CVO4-3)") (class "Default")
      (node (ref "CVO4") (pin "1") (pinfunction "3_1") (pintype "passive"))
      (node (ref "NT1") (pin "P$1") (pinfunction "2_P$1") (pintype "passive"))
    )
    (net (code "47") (name "Net-(CVO5-3)") (class "Default")
      (node (ref "CVO5") (pin "1") (pinfunction "3_1") (pintype "passive"))
      (node (ref "TO4") (pin "P$1") (pinfunction "2_P$1") (pintype "passive"))
    )
    (net (code "48") (name "Net-(CVO6-3)") (class "Default")
      (node (ref "CVO6") (pin "1") (pinfunction "3_1") (pintype "passive"))
      (node (ref "TO3") (pin "P$1") (pinfunction "2_P$1") (pintype "passive"))
    )
    (net (code "49") (name "Net-(CVO7-3)") (class "Default")
      (node (ref "CVO7") (pin "1") (pinfunction "3_1") (pintype "passive"))
      (node (ref "TO2") (pin "P$1") (pinfunction "2_P$1") (pintype "passive"))
    )
    (net (code "50") (name "Net-(CVO8-3)") (class "Default")
      (node (ref "CVO8") (pin "1") (pinfunction "3_1") (pintype "passive"))
      (node (ref "TO1") (pin "P$1") (pinfunction "2_P$1") (pintype "passive"))
    )
    (net (code "51") (name "Net-(Q1-B)") (class "Default")
      (node (ref "Q1") (pin "1") (pinfunction "B_1") (pintype "passive"))
      (node (ref "R1") (pin "2") (pinfunction "2_2") (pintype "passive"))
      (node (ref "R5") (pin "2") (pinfunction "2_2") (pintype "passive"))
    )
    (net (code "52") (name "Net-(Q2-B)") (class "Default")
      (node (ref "Q2") (pin "1") (pinfunction "B_1") (pintype "passive"))
      (node (ref "R2") (pin "2") (pinfunction "2_2") (pintype "passive"))
      (node (ref "R6") (pin "2") (pinfunction "2_2") (pintype "passive"))
    )
    (net (code "53") (name "Net-(Q3-B)") (class "Default")
      (node (ref "Q3") (pin "1") (pinfunction "B_1") (pintype "passive"))
      (node (ref "R3") (pin "2") (pinfunction "2_2") (pintype "passive"))
      (node (ref "R7") (pin "2") (pinfunction "2_2") (pintype "passive"))
    )
    (net (code "54") (name "Net-(Q4-B)") (class "Default")
      (node (ref "Q4") (pin "1") (pinfunction "B_1") (pintype "passive"))
      (node (ref "R4") (pin "2") (pinfunction "2_2") (pintype "passive"))
      (node (ref "R8") (pin "2") (pinfunction "2_2") (pintype "passive"))
    )
    (net (code "55") (name "Net-(R9-Pad1)") (class "Default")
      (node (ref "R9") (pin "1") (pinfunction "1_1") (pintype "passive"))
      (node (ref "S1") (pin "A") (pinfunction "A_A") (pintype "passive"))
    )
    (net (code "56") (name "Net-(R10-Pad1)") (class "Default")
      (node (ref "R10") (pin "1") (pinfunction "1_1") (pintype "passive"))
      (node (ref "S2") (pin "A") (pinfunction "A_A") (pintype "passive"))
    )
    (net (code "57") (name "Net-(R11-Pad1)") (class "Default")
      (node (ref "R11") (pin "1") (pinfunction "1_1") (pintype "passive"))
      (node (ref "S3") (pin "A") (pinfunction "A_A") (pintype "passive"))
    )
    (net (code "58") (name "Net-(R12-Pad1)") (class "Default")
      (node (ref "R12") (pin "1") (pinfunction "1_1") (pintype "passive"))
      (node (ref "S4") (pin "A") (pinfunction "A_A") (pintype "passive"))
    )
    (net (code "59") (name "Net-(TI1-2)") (class "Default")
      (node (ref "R1") (pin "1") (pinfunction "1_1") (pintype "passive"))
      (node (ref "TI1") (pin "P$1") (pinfunction "2_P$1") (pintype "passive"))
    )
    (net (code "60") (name "Net-(TI2-2)") (class "Default")
      (node (ref "R2") (pin "1") (pinfunction "1_1") (pintype "passive"))
      (node (ref "TI2") (pin "P$1") (pinfunction "2_P$1") (pintype "passive"))
    )
    (net (code "61") (name "Net-(TI3-2)") (class "Default")
      (node (ref "R3") (pin "1") (pinfunction "1_1") (pintype "passive"))
      (node (ref "TI3") (pin "P$1") (pinfunction "2_P$1") (pintype "passive"))
    )
    (net (code "62") (name "Net-(TI4-2)") (class "Default")
      (node (ref "R4") (pin "1") (pinfunction "1_1") (pintype "passive"))
      (node (ref "TI4") (pin "P$1") (pinfunction "2_P$1") (pintype "passive"))
    )
    (net (code "63") (name "unconnected-(+5V-3-Pad1)") (class "Default")
      (node (ref "+5V") (pin "1") (pinfunction "3_1") (pintype "passive"))
    )
    (net (code "64") (name "unconnected-(-5V-3-Pad1)") (class "Default")
      (node (ref "-5V") (pin "1") (pinfunction "3_1") (pintype "passive"))
    )
    (net (code "65") (name "unconnected-(8_DAC_CS-3-Pad1)") (class "Default")
      (node (ref "8_DAC_CS") (pin "1") (pinfunction "3_1") (pintype "passive"))
    )
    (net (code "66") (name "unconnected-(9_DAC_CS-3-Pad1)") (class "Default")
      (node (ref "9_DAC_CS") (pin "1") (pinfunction "3_1") (pintype "passive"))
    )
    (net (code "67") (name "unconnected-(10_CS-3-Pad1)") (class "Default")
      (node (ref "10_CS") (pin "1") (pinfunction "3_1") (pintype "passive"))
    )
    (net (code "68") (name "unconnected-(18_A4_SDA-3-Pad1)") (class "Default")
      (node (ref "18_A4_SDA") (pin "1") (pinfunction "3_1") (pintype "passive"))
    )
    (net (code "69") (name "unconnected-(19_A5_SCL-3-Pad1)") (class "Default")
      (node (ref "19_A5_SCL") (pin "1") (pinfunction "3_1") (pintype "passive"))
    )
    (net (code "70") (name "unconnected-(CV1_-3-Pad1)") (class "Default")
      (node (ref "CV1_") (pin "1") (pinfunction "3_1") (pintype "passive"))
    )
    (net (code "71") (name "unconnected-(CV2_-3-Pad1)") (class "Default")
      (node (ref "CV2_") (pin "1") (pinfunction "3_1") (pintype "passive"))
    )
    (net (code "72") (name "unconnected-(CV3_-3-Pad1)") (class "Default")
      (node (ref "CV3_") (pin "1") (pinfunction "3_1") (pintype "passive"))
    )
    (net (code "73") (name "unconnected-(CV4_-3-Pad1)") (class "Default")
      (node (ref "CV4_") (pin "1") (pinfunction "3_1") (pintype "passive"))
    )
    (net (code "74") (name "unconnected-(CV5_-3-Pad1)") (class "Default")
      (node (ref "CV5_") (pin "1") (pinfunction "3_1") (pintype "passive"))
    )
    (net (code "75") (name "unconnected-(CV6_-3-Pad1)") (class "Default")
      (node (ref "CV6_") (pin "1") (pinfunction "3_1") (pintype "passive"))
    )
    (net (code "76") (name "unconnected-(CV7_-3-Pad1)") (class "Default")
      (node (ref "CV7_") (pin "1") (pinfunction "3_1") (pintype "passive"))
    )
    (net (code "77") (name "unconnected-(CV8_-3-Pad1)") (class "Default")
      (node (ref "CV8_") (pin "1") (pinfunction "3_1") (pintype "passive"))
    )
    (net (code "78") (name "unconnected-(IN1-3-PadP$2)") (class "Default")
      (node (ref "IN1") (pin "P$2") (pinfunction "3_P$2") (pintype "passive"))
    )
    (net (code "79") (name "unconnected-(IN2-3-PadP$2)") (class "Default")
      (node (ref "IN2") (pin "P$2") (pinfunction "3_P$2") (pintype "passive"))
    )
    (net (code "80") (name "unconnected-(IN3-3-PadP$2)") (class "Default")
      (node (ref "IN3") (pin "P$2") (pinfunction "3_P$2") (pintype "passive"))
    )
    (net (code "81") (name "unconnected-(IN4-3-PadP$2)") (class "Default")
      (node (ref "IN4") (pin "P$2") (pinfunction "3_P$2") (pintype "passive"))
    )
    (net (code "82") (name "unconnected-(NT1-3-PadP$2)") (class "Default")
      (node (ref "NT1") (pin "P$2") (pinfunction "3_P$2") (pintype "passive"))
    )
    (net (code "83") (name "unconnected-(NT2-3-PadP$2)") (class "Default")
      (node (ref "NT2") (pin "P$2") (pinfunction "3_P$2") (pintype "passive"))
    )
    (net (code "84") (name "unconnected-(NT3-3-PadP$2)") (class "Default")
      (node (ref "NT3") (pin "P$2") (pinfunction "3_P$2") (pintype "passive"))
    )
    (net (code "85") (name "unconnected-(NT4-3-PadP$2)") (class "Default")
      (node (ref "NT4") (pin "P$2") (pinfunction "3_P$2") (pintype "passive"))
    )
    (net (code "86") (name "unconnected-(OFFSET-3-Pad1)") (class "Default")
      (node (ref "OFFSET") (pin "1") (pinfunction "3_1") (pintype "passive"))
    )
    (net (code "87") (name "unconnected-(S1-S1-Pad2)") (class "Default")
      (node (ref "S1") (pin "2") (pinfunction "S1_2") (pintype "passive"))
    )
    (net (code "88") (name "unconnected-(S2-S1-Pad2)") (class "Default")
      (node (ref "S2") (pin "2") (pinfunction "S1_2") (pintype "passive"))
    )
    (net (code "89") (name "unconnected-(S3-S1-Pad2)") (class "Default")
      (node (ref "S3") (pin "2") (pinfunction "S1_2") (pintype "passive"))
    )
    (net (code "90") (name "unconnected-(S4-S1-Pad2)") (class "Default")
      (node (ref "S4") (pin "2") (pinfunction "S1_2") (pintype "passive"))
    )
    (net (code "91") (name "unconnected-(TFT1-PadBLK)") (class "Default")
      (node (ref "TFT1") (pin "BLK") (pinfunction "BLK_BLK") (pintype "bidirectional"))
    )
    (net (code "92") (name "unconnected-(TI1-3-PadP$2)") (class "Default")
      (node (ref "TI1") (pin "P$2") (pinfunction "3_P$2") (pintype "passive"))
    )
    (net (code "93") (name "unconnected-(TI2-3-PadP$2)") (class "Default")
      (node (ref "TI2") (pin "P$2") (pinfunction "3_P$2") (pintype "passive"))
    )
    (net (code "94") (name "unconnected-(TI3-3-PadP$2)") (class "Default")
      (node (ref "TI3") (pin "P$2") (pinfunction "3_P$2") (pintype "passive"))
    )
    (net (code "95") (name "unconnected-(TI4-3-PadP$2)") (class "Default")
      (node (ref "TI4") (pin "P$2") (pinfunction "3_P$2") (pintype "passive"))
    )
    (net (code "96") (name "unconnected-(TO1-3-PadP$2)") (class "Default")
      (node (ref "TO1") (pin "P$2") (pinfunction "3_P$2") (pintype "passive"))
    )
    (net (code "97") (name "unconnected-(TO2-3-PadP$2)") (class "Default")
      (node (ref "TO2") (pin "P$2") (pinfunction "3_P$2") (pintype "passive"))
    )
    (net (code "98") (name "unconnected-(TO3-3-PadP$2)") (class "Default")
      (node (ref "TO3") (pin "P$2") (pinfunction "3_P$2") (pintype "passive"))
    )
    (net (code "99") (name "unconnected-(TO4-3-PadP$2)") (class "Default")
      (node (ref "TO4") (pin "P$2") (pinfunction "3_P$2") (pintype "passive"))
    )
    (net (code "100") (name "unconnected-(U$2-NC-PadP$1)") (class "Default")
      (node (ref "U$2") (pin "P$1") (pinfunction "NC_P$1") (pintype "bidirectional"))
    )
    (net (code "101") (name "unconnected-(U$2-RSV-PadP$8)") (class "Default")
      (node (ref "U$2") (pin "P$8") (pinfunction "RSV_P$8") (pintype "bidirectional"))
    )
  )
)
